# E104-BT11G-PCB.net
KiCad netlist of a schematic drawn in EAGLE
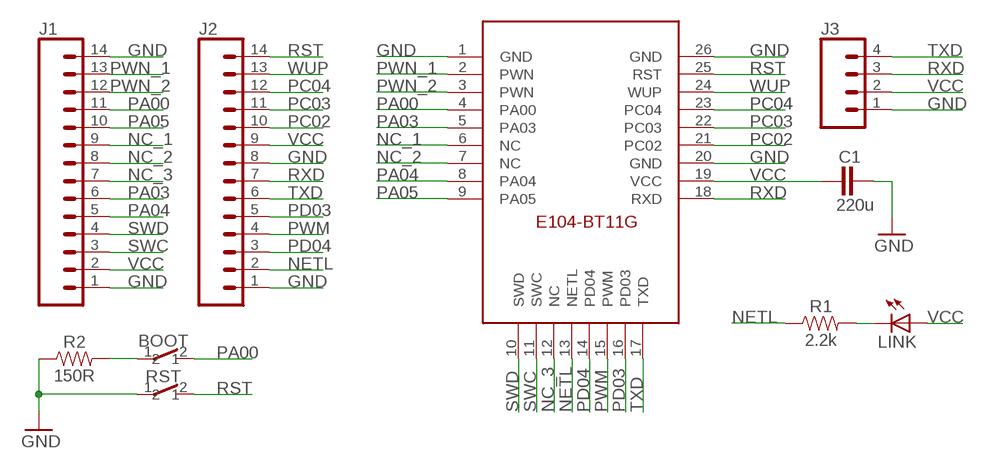
[diagram p0: schematic, sheet 1]

(export (version "E")
  (design (tool "Eeschema 10.0.6"))
  (components
    (comp (ref "BOOT")
      (value "SKRKAEE010")
      (footprint "eagle-import:SKRK")
      (fields (field (name "MF") "ALPS"))
      (libsource (lib "eagle-import") (part "SKRKAEE010"))
    )
    (comp (ref "C1")
      (value "220u")
      (footprint "eagle-import:CAPM3528X210")
      (libsource (lib "eagle-import") (part "CTANTALUM-1411(3528-METRIC)_"))
    )
    (comp (ref "J1")
      (value "CONN_14NO_SILK")
      (footprint "eagle-import:1X14_NO_SILK")
      (libsource (lib "eagle-import") (part "CONN_14NO_SILK"))
    )
    (comp (ref "J2")
      (value "CONN_14NO_SILK")
      (footprint "eagle-import:1X14_NO_SILK")
      (libsource (lib "eagle-import") (part "CONN_14NO_SILK"))
    )
    (comp (ref "J3")
      (value "CONN_041X04_NO_SILK")
      (footprint "eagle-import:1X04_NO_SILK")
      (libsource (lib "eagle-import") (part "CONN_041X04_NO_SILK"))
    )
    (comp (ref "LINK")
      (value "LEDCHIP-LED0603")
      (footprint "eagle-import:CHIP-LED0603")
      (libsource (lib "eagle-import") (part "LEDCHIP-LED0603"))
    )
    (comp (ref "R1")
      (value "2.2k")
      (footprint "eagle-import:0603")
      (libsource (lib "eagle-import") (part "2.2KOHM-0603-1/10W-1%"))
    )
    (comp (ref "R2")
      (value "150R")
      (footprint "eagle-import:0603")
      (libsource (lib "eagle-import") (part "2.2KOHM-0603-1/10W-1%"))
    )
    (comp (ref "RST")
      (value "SKRKAEE010")
      (footprint "eagle-import:SKRK")
      (fields (field (name "MF") "ALPS"))
      (libsource (lib "eagle-import") (part "SKRKAEE010"))
    )
    (comp (ref "U$1")
      (value "E104-BT11G-PCBPCB")
      (footprint "eagle-import:E104-BT11G-PCB")
      (libsource (lib "eagle-import") (part "E104-BT11G-PCBPCB"))
    )
  )
  (nets
    (net (code "1") (name "/NC_1") (class "Default")
      (node (ref "J1") (pin "9") (pinfunction "9_9") (pintype "passive"))
      (node (ref "U$1") (pin "6") (pinfunction "NC_6") (pintype "bidirectional"))
    )
    (net (code "2") (name "/NC_2") (class "Default")
      (node (ref "J1") (pin "8") (pinfunction "8_8") (pintype "passive"))
      (node (ref "U$1") (pin "7") (pinfunction "NC_7") (pintype "bidirectional"))
    )
    (net (code "3") (name "/NC_3") (class "Default")
      (node (ref "J1") (pin "7") (pinfunction "7_7") (pintype "passive"))
      (node (ref "U$1") (pin "12") (pinfunction "NC_12") (pintype "bidirectional"))
    )
    (net (code "4") (name "/NETL") (class "Default")
      (node (ref "J2") (pin "2") (pinfunction "2_2") (pintype "passive"))
      (node (ref "R1") (pin "1") (pinfunction "1_1") (pintype "passive"))
      (node (ref "U$1") (pin "13") (pinfunction "NETL_13") (pintype "bidirectional"))
    )
    (net (code "5") (name "/PA00") (class "Default")
      (node (ref "BOOT") (pin "2") (pinfunction "2_2") (pintype "passive"))
      (node (ref "J1") (pin "11") (pinfunction "11_11") (pintype "passive"))
      (node (ref "U$1") (pin "4") (pinfunction "PA00_4") (pintype "bidirectional"))
    )
    (net (code "6") (name "/PA03") (class "Default")
      (node (ref "J1") (pin "6") (pinfunction "6_6") (pintype "passive"))
      (node (ref "U$1") (pin "5") (pinfunction "PA03_5") (pintype "bidirectional"))
    )
    (net (code "7") (name "/PA04") (class "Default")
      (node (ref "J1") (pin "5") (pinfunction "5_5") (pintype "passive"))
      (node (ref "U$1") (pin "8") (pinfunction "PA04_8") (pintype "bidirectional"))
    )
    (net (code "8") (name "/PA05") (class "Default")
      (node (ref "J1") (pin "10") (pinfunction "10_10") (pintype "passive"))
      (node (ref "U$1") (pin "9") (pinfunction "PA05_9") (pintype "bidirectional"))
    )
    (net (code "9") (name "/PC02") (class "Default")
      (node (ref "J2") (pin "10") (pinfunction "10_10") (pintype "passive"))
      (node (ref "U$1") (pin "21") (pinfunction "PC02_21") (pintype "bidirectional"))
    )
    (net (code "10") (name "/PC03") (class "Default")
      (node (ref "J2") (pin "11") (pinfunction "11_11") (pintype "passive"))
      (node (ref "U$1") (pin "22") (pinfunction "PC03_22") (pintype "bidirectional"))
    )
    (net (code "11") (name "/PC04") (class "Default")
      (node (ref "J2") (pin "12") (pinfunction "12_12") (pintype "passive"))
      (node (ref "U$1") (pin "23") (pinfunction "PC04_23") (pintype "bidirectional"))
    )
    (net (code "12") (name "/PD03") (class "Default")
      (node (ref "J2") (pin "5") (pinfunction "5_5") (pintype "passive"))
      (node (ref "U$1") (pin "16") (pinfunction "PD03_16") (pintype "bidirectional"))
    )
    (net (code "13") (name "/PD04") (class "Default")
      (node (ref "J2") (pin "3") (pinfunction "3_3") (pintype "passive"))
      (node (ref "U$1") (pin "14") (pinfunction "PD04_14") (pintype "bidirectional"))
    )
    (net (code "14") (name "/PWM") (class "Default")
      (node (ref "J2") (pin "4") (pinfunction "4_4") (pintype "passive"))
      (node (ref "U$1") (pin "15") (pinfunction "PWM_15") (pintype "bidirectional"))
    )
    (net (code "15") (name "/PWN_1") (class "Default")
      (node (ref "J1") (pin "13") (pinfunction "13_13") (pintype "passive"))
      (node (ref "U$1") (pin "2") (pinfunction "PWN_2") (pintype "bidirectional"))
    )
    (net (code "16") (name "/PWN_2") (class "Default")
      (node (ref "J1") (pin "12") (pinfunction "12_12") (pintype "passive"))
      (node (ref "U$1") (pin "3") (pinfunction "PWN_3") (pintype "bidirectional"))
    )
    (net (code "17") (name "/RST") (class "Default")
      (node (ref "J2") (pin "14") (pinfunction "14_14") (pintype "passive"))
      (node (ref "RST") (pin "2") (pinfunction "2_2") (pintype "passive"))
      (node (ref "U$1") (pin "25") (pinfunction "RST_25") (pintype "bidirectional"))
    )
    (net (code "18") (name "/RXD") (class "Default")
      (node (ref "J2") (pin "7") (pinfunction "7_7") (pintype "passive"))
      (node (ref "J3") (pin "3") (pinfunction "3_3") (pintype "passive"))
      (node (ref "U$1") (pin "18") (pinfunction "RXD_18") (pintype "bidirectional"))
    )
    (net (code "19") (name "/SWC") (class "Default")
      (node (ref "J1") (pin "3") (pinfunction "3_3") (pintype "passive"))
      (node (ref "U$1") (pin "11") (pinfunction "SWC_11") (pintype "bidirectional"))
    )
    (net (code "20") (name "/SWD") (class "Default")
      (node (ref "J1") (pin "4") (pinfunction "4_4") (pintype "passive"))
      (node (ref "U$1") (pin "10") (pinfunction "SWD_10") (pintype "bidirectional"))
    )
    (net (code "21") (name "/TXD") (class "Default")
      (node (ref "J2") (pin "6") (pinfunction "6_6") (pintype "passive"))
      (node (ref "J3") (pin "4") (pinfunction "4_4") (pintype "passive"))
      (node (ref "U$1") (pin "17") (pinfunction "TXD_17") (pintype "bidirectional"))
    )
    (net (code "22") (name "/VCC") (class "Default")
      (node (ref "C1") (pin "1") (pinfunction "1_1") (pintype "passive"))
      (node (ref "J1") (pin "2") (pinfunction "2_2") (pintype "passive"))
      (node (ref "J2") (pin "9") (pinfunction "9_9") (pintype "passive"))
      (node (ref "J3") (pin "2") (pinfunction "2_2") (pintype "passive"))
      (node (ref "LINK") (pin "A") (pinfunction "A_A") (pintype "passive"))
      (node (ref "U$1") (pin "19") (pinfunction "VCC_19") (pintype "bidirectional"))
    )
    (net (code "23") (name "/WUP") (class "Default")
      (node (ref "J2") (pin "13") (pinfunction "13_13") (pintype "passive"))
      (node (ref "U$1") (pin "24") (pinfunction "WUP_24") (pintype "bidirectional"))
    )
    (net (code "24") (name "GND") (class "Default")
      (node (ref "C1") (pin "2") (pinfunction "2_2") (pintype "passive"))
      (node (ref "J1") (pin "1") (pinfunction "1_1") (pintype "passive"))
      (node (ref "J1") (pin "14") (pinfunction "14_14") (pintype "passive"))
      (node (ref "J2") (pin "1") (pinfunction "1_1") (pintype "passive"))
      (node (ref "J2") (pin "8") (pinfunction "8_8") (pintype "passive"))
      (node (ref "J3") (pin "1") (pinfunction "1_1") (pintype "passive"))
      (node (ref "R2") (pin "1") (pinfunction "1_1") (pintype "passive"))
      (node (ref "RST") (pin "1") (pinfunction "1_1") (pintype "passive"))
      (node (ref "U$1") (pin "1") (pinfunction "GND_1") (pintype "bidirectional"))
      (node (ref "U$1") (pin "20") (pinfunction "GND_20") (pintype "bidirectional"))
      (node (ref "U$1") (pin "26") (pinfunction "GND_26") (pintype "bidirectional"))
    )
    (net (code "25") (name "Net-(BOOT-Pad1)") (class "Default")
      (node (ref "BOOT") (pin "1") (pinfunction "1_1") (pintype "passive"))
      (node (ref "R2") (pin "2") (pinfunction "2_2") (pintype "passive"))
    )
    (net (code "26") (name "Net-(LINK-PadC)") (class "Default")
      (node (ref "LINK") (pin "C") (pinfunction "C_C") (pintype "passive"))
      (node (ref "R1") (pin "2") (pinfunction "2_2") (pintype "passive"))
    )
  )
)
